# TPS5430.net
KiCad netlist of a schematic drawn in EasyEDA Pro
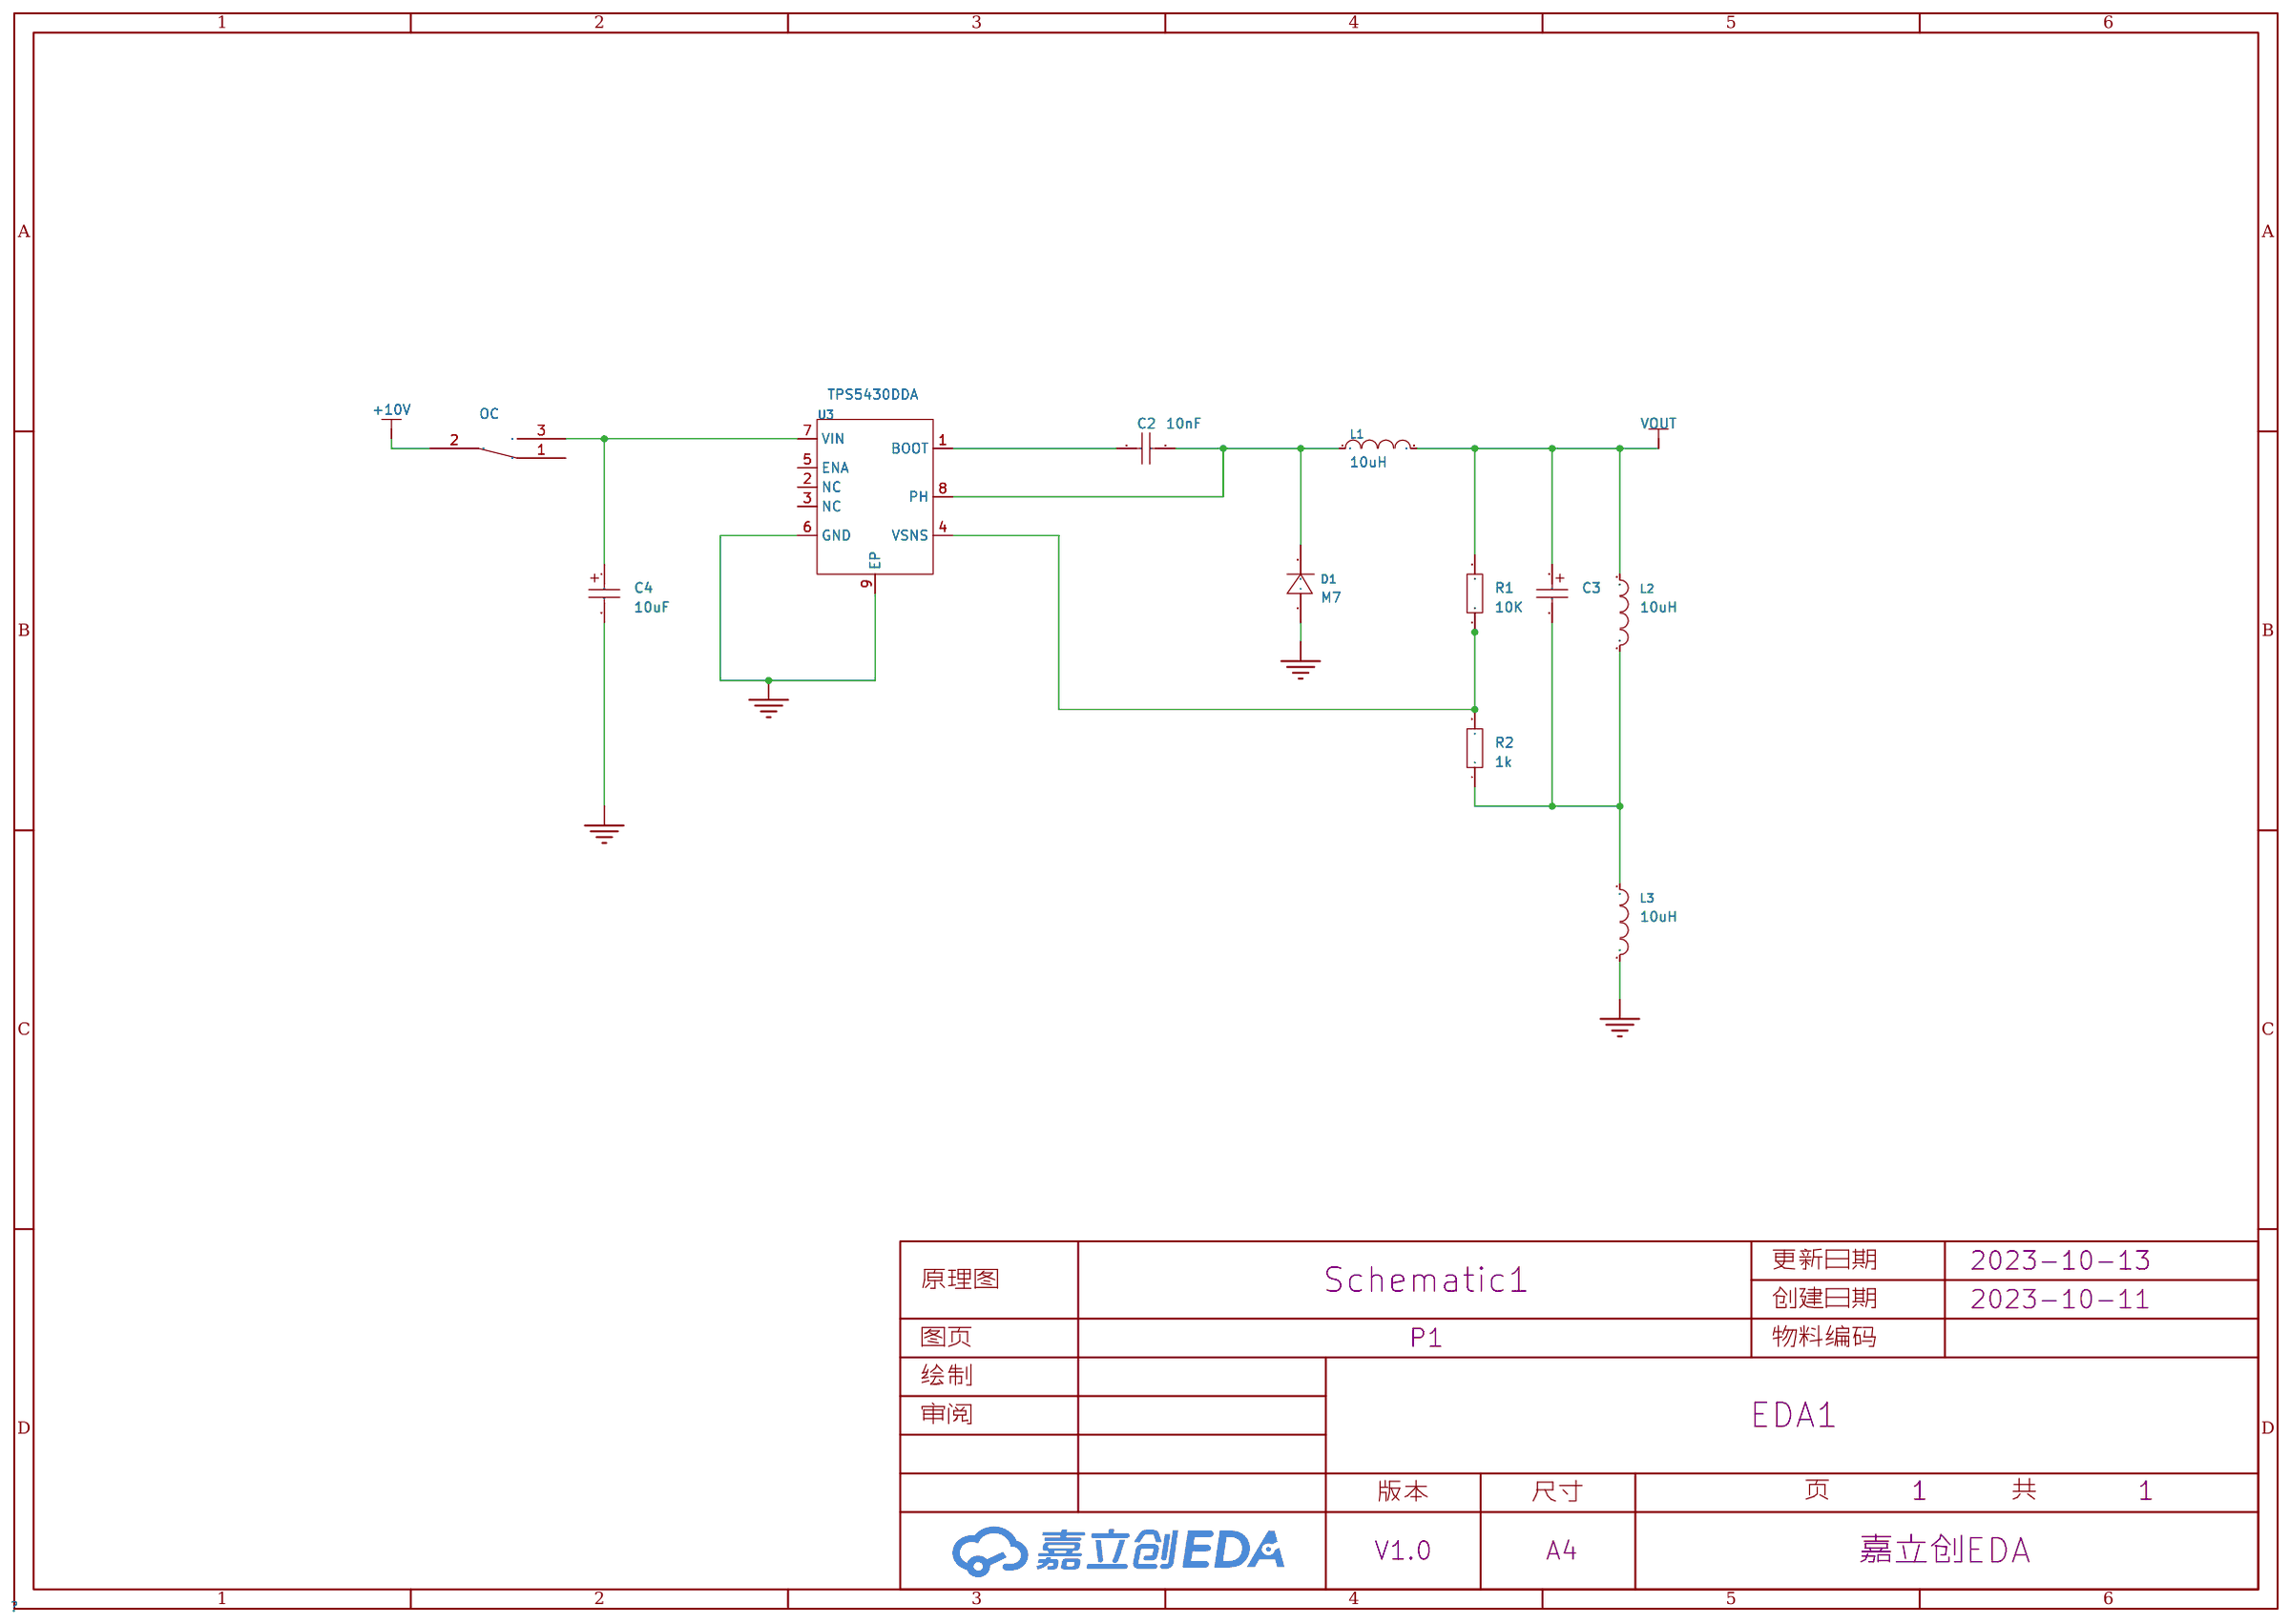
[diagram p0: schematic sheet]

(export (version "E")
  (design (tool "Eeschema 10.0.6"))
  (components
    (comp (ref "C2")
      (value "10nF")
      (footprint "easyedapro:C0402")
      (description "容值:10nF;精度:±10%;额定电压:50V;材质(温度系数):X7R;")
      (fields
        (field (name "Manufacturer Part") "CC0402KRX7R9BB103")
        (field (name "Manufacturer") "YAGEO(国巨)")
      )
      (libsource (lib "easyedapro") (part "CC0402KRX7R9BB103"))
    )
    (comp (ref "C3")
      (value "10uF")
      (footprint "easyedapro:CAP-SMD_L3.2-W1.6-RD")
      (description "容值:10uF;精度:±10%;额定电压:16V;等效串联电阻:10Ω@100kHz;")
      (fields
        (field (name "Manufacturer Part") "CA45-A-16V-10uF-K")
        (field (name "Manufacturer") "CEC(振华新云)")
      )
      (libsource (lib "easyedapro") (part "CA45-A-16V-10UF-K"))
    )
    (comp (ref "C4")
      (value "10uF")
      (footprint "easyedapro:CAP-SMD_L3.2-W1.6-RD-C7171")
      (description "容值:10uF;精度:±10%;额定电压:16V;等效串联电阻:3Ω@100kHz;")
      (fields (field (name "Manufacturer Part") "TAJA106K016RNJ") (field (name "Manufacturer") "Kyocera AVX"))
      (libsource (lib "easyedapro") (part "TAJA106K016RNJ"))
    )
    (comp (ref "D1")
      (value "M7")
      (footprint "easyedapro:SMA_L4.3-W2.6-LS5.2-RD")
      (description "二极管配置:-;直流反向耐压(Vr):1kV;平均整流电流(Io):1A;正向压降(Vf):1.1V@1A;")
      (fields (field (name "Manufacturer") "MDD"))
      (libsource (lib "easyedapro") (part "M7_C95872"))
    )
    (comp (ref "L1")
      (value "10uH")
      (footprint "easyedapro:L0603")
      (description "电感值:10uH;精度:±10%;额定电流:3mA;饱和电流(Isat):-;直流电阻(DCR):1.85Ω;")
      (fields
        (field (name "Manufacturer Part") "SDFL1608S100KTF")
        (field (name "Manufacturer") "Sunlord(顺络)")
      )
      (libsource (lib "easyedapro") (part "SDFL1608S100KTF"))
    )
    (comp (ref "L2")
      (value "10uH")
      (footprint "easyedapro:L0603")
      (description "电感值:10uH;精度:±10%;额定电流:3mA;饱和电流(Isat):-;直流电阻(DCR):1.85Ω;")
      (fields
        (field (name "Manufacturer Part") "SDFL1608S100KTF")
        (field (name "Manufacturer") "Sunlord(顺络)")
      )
      (libsource (lib "easyedapro") (part "SDFL1608S100KTF"))
    )
    (comp (ref "L3")
      (value "10uH")
      (footprint "easyedapro:L0603")
      (description "电感值:10uH;精度:±10%;额定电流:3mA;饱和电流(Isat):-;直流电阻(DCR):1.85Ω;")
      (fields
        (field (name "Manufacturer Part") "SDFL1608S100KTF")
        (field (name "Manufacturer") "Sunlord(顺络)")
      )
      (libsource (lib "easyedapro") (part "SDFL1608S100KTF"))
    )
    (comp (ref "OC")
      (value "MT-0-102-A101-M200-RS")
      (footprint "easyedapro:SW-TH_MT-0-103-A101-M200-RS")
      (description "额定电流:5A;额定电压(AC):125V;电路结构:单刀双掷;机械寿命:-;安装方式:直插;")
      (fields (field (name "Manufacturer") "YUEN FUNG(源丰)"))
      (libsource (lib "easyedapro") (part "MT-0-102-A101-M200-RS+PJ"))
    )
    (comp (ref "R1") (value "10K") (footprint "easyedapro:R0603") (libsource (lib "easyedapro") (part "电阻")))
    (comp (ref "R2") (value "1k") (footprint "easyedapro:R0603") (libsource (lib "easyedapro") (part "电阻")))
    (comp (ref "U3")
      (value "TPS5430DDA")
      (footprint "easyedapro:ESOP-8_L4.9-W3.9-P1.27-LS6.0-BL-EP-2")
      (description "功能类型:降压型;输出类型:可调;输入电压:5.5V~36V;输出电压:1.221V~32.04V;输出电流(最大值):3A;")
      (fields (field (name "Manufacturer") "TI(德州仪器)"))
      (libsource (lib "easyedapro") (part "TPS5430DDA"))
    )
  )
  (nets
    (net (code "1") (name "+10V") (class "Default")
      (node (ref "OC") (pin "2") (pinfunction "2_2") (pintype "unspecified"))
    )
    (net (code "2") (name "GND") (class "Default")
      (node (ref "C4") (pin "2") (pinfunction "2_2") (pintype "input"))
      (node (ref "D1") (pin "2") (pinfunction "A_2") (pintype "input"))
      (node (ref "L3") (pin "2") (pinfunction "2_2") (pintype "input"))
      (node (ref "U3") (pin "6") (pinfunction "GND_6") (pintype "input"))
      (node (ref "U3") (pin "9") (pinfunction "EP_9") (pintype "input"))
    )
    (net (code "3") (name "Net-(C3-Pad2)") (class "Default")
      (node (ref "C3") (pin "2") (pinfunction "2_2") (pintype "input"))
      (node (ref "L2") (pin "2") (pinfunction "2_2") (pintype "input"))
      (node (ref "L3") (pin "1") (pinfunction "1_1") (pintype "input"))
      (node (ref "R2") (pin "1") (pinfunction "1_1") (pintype "input"))
    )
    (net (code "4") (name "Net-(D1-K)") (class "Default")
      (node (ref "C2") (pin "2") (pinfunction "2_2") (pintype "input"))
      (node (ref "D1") (pin "1") (pinfunction "K_1") (pintype "input"))
      (node (ref "L1") (pin "1") (pinfunction "1_1") (pintype "input"))
      (node (ref "U3") (pin "8") (pinfunction "PH_8") (pintype "input"))
    )
    (net (code "5") (name "Net-(U3-BOOT)") (class "Default")
      (node (ref "C2") (pin "1") (pinfunction "1_1") (pintype "input"))
      (node (ref "U3") (pin "1") (pinfunction "BOOT_1") (pintype "input"))
    )
    (net (code "6") (name "Net-(U3-VIN)") (class "Default")
      (node (ref "C4") (pin "1") (pinfunction "1_1") (pintype "input"))
      (node (ref "OC") (pin "3") (pinfunction "3_3") (pintype "unspecified"))
      (node (ref "U3") (pin "7") (pinfunction "VIN_7") (pintype "input"))
    )
    (net (code "7") (name "Net-(U3-VSNS)") (class "Default")
      (node (ref "R1") (pin "1") (pinfunction "1_1") (pintype "input"))
      (node (ref "R2") (pin "2") (pinfunction "2_2") (pintype "input"))
      (node (ref "U3") (pin "4") (pinfunction "VSNS_4") (pintype "input"))
    )
    (net (code "8") (name "VOUT") (class "Default")
      (node (ref "C3") (pin "1") (pinfunction "1_1") (pintype "input"))
      (node (ref "L1") (pin "2") (pinfunction "2_2") (pintype "input"))
      (node (ref "L2") (pin "1") (pinfunction "1_1") (pintype "input"))
      (node (ref "R1") (pin "2") (pinfunction "2_2") (pintype "input"))
    )
    (net (code "9") (name "unconnected-(OC-Pad1)") (class "Default")
      (node (ref "OC") (pin "1") (pinfunction "1_1") (pintype "unspecified"))
    )
    (net (code "10") (name "unconnected-(U3-ENA-Pad5)") (class "Default")
      (node (ref "U3") (pin "5") (pinfunction "ENA_5") (pintype "input"))
    )
    (net (code "11") (name "unconnected-(U3-NC-Pad2)") (class "Default")
      (node (ref "U3") (pin "2") (pinfunction "NC_2") (pintype "input"))
    )
    (net (code "12") (name "unconnected-(U3-NC-Pad3)") (class "Default")
      (node (ref "U3") (pin "3") (pinfunction "NC_3") (pintype "input"))
    )
  )
)
